# 4_-RF.net
KiCad netlist of a schematic drawn in Altium Designer
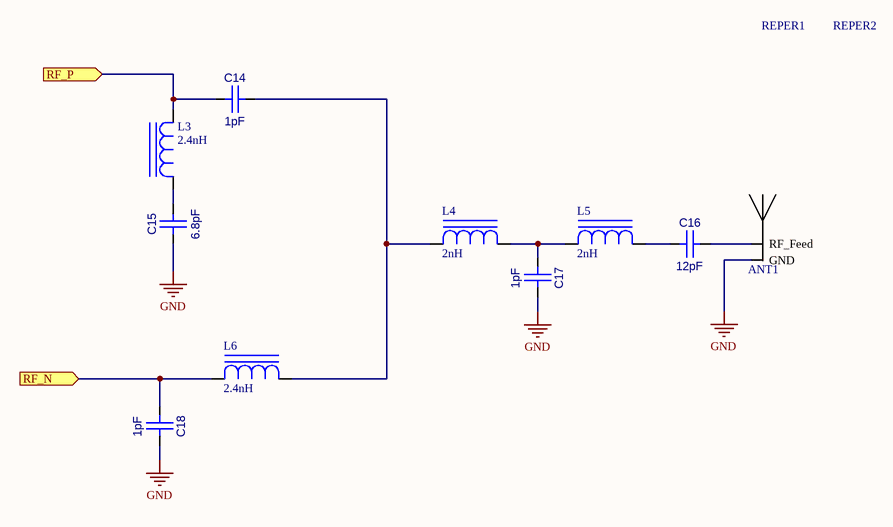
[diagram p0: [4]-RF.SchDoc]

(export (version "E")
  (design (tool "Eeschema 10.0.6"))
  (components
    (comp (ref "ANT1")
      (value "IFA_TI_2.4G_Reference")
      (footprint "ANT_IFA_2.4G_BEST")
      (libsource (lib "gprs_modem_2") (part "ANT_WiFi_IFA_BEST"))
    )
    (comp (ref "C14")
      (value "1pF")
      (footprint "CC0603")
      (description "CC0603")
      (libsource (lib "gprs_modem_2") (part "CC0603"))
    )
    (comp (ref "C15")
      (value "6.8pF")
      (footprint "CC0603")
      (description "CC0603")
      (libsource (lib "gprs_modem_2") (part "CC0603"))
    )
    (comp (ref "C16")
      (value "12pF")
      (footprint "CC0603")
      (description "CC0603")
      (libsource (lib "gprs_modem_2") (part "CC0603"))
    )
    (comp (ref "C17")
      (value "1pF")
      (footprint "CC0603")
      (description "CC0603")
      (libsource (lib "gprs_modem_2") (part "CC0603"))
    )
    (comp (ref "C18")
      (value "1pF")
      (footprint "CC0603")
      (description "CC0603")
      (libsource (lib "gprs_modem_2") (part "CC0603"))
    )
    (comp (ref "L3")
      (value "2.4nH")
      (footprint "L0402")
      (description "L0402")
      (libsource (lib "gprs_modem_2") (part "L0402"))
    )
    (comp (ref "L4")
      (value "2nH")
      (footprint "L0402")
      (description "L0402")
      (libsource (lib "gprs_modem_2") (part "L0402"))
    )
    (comp (ref "L5")
      (value "2nH")
      (footprint "L0402")
      (description "L0402")
      (libsource (lib "gprs_modem_2") (part "L0402"))
    )
    (comp (ref "L6")
      (value "2.4nH")
      (footprint "L0402")
      (description "L0402")
      (libsource (lib "gprs_modem_2") (part "L0402"))
    )
    (comp (ref "REPER1")
      (value "REPER1.2")
      (footprint "REPER1.2")
      (libsource (lib "gprs_modem_2") (part "REPER1.2"))
    )
    (comp (ref "REPER2")
      (value "REPER1.2")
      (footprint "REPER1.2")
      (libsource (lib "gprs_modem_2") (part "REPER1.2"))
    )
  )
  (nets
    (net (code "1") (name "/RF_N") (class "Default")
      (node (ref "C18") (pin "1") (pinfunction "A_1") (pintype "passive"))
      (node (ref "L6") (pin "1") (pinfunction "A_1") (pintype "passive"))
    )
    (net (code "2") (name "/RF_P") (class "Default")
      (node (ref "C14") (pin "1") (pinfunction "A_1") (pintype "passive"))
      (node (ref "L3") (pin "2") (pinfunction "C_2") (pintype "passive"))
    )
    (net (code "3") (name "GND") (class "Default")
      (node (ref "ANT1") (pin "2") (pinfunction "GND_2") (pintype "passive"))
      (node (ref "C15") (pin "1") (pinfunction "A_1") (pintype "passive"))
      (node (ref "C17") (pin "2") (pinfunction "B_2") (pintype "passive"))
      (node (ref "C18") (pin "2") (pinfunction "B_2") (pintype "passive"))
    )
    (net (code "4") (name "Net-(ANT1-RF_Feed)") (class "Default")
      (node (ref "ANT1") (pin "1") (pinfunction "RF_Feed_1") (pintype "passive"))
      (node (ref "C16") (pin "2") (pinfunction "B_2") (pintype "passive"))
    )
    (net (code "5") (name "Net-(C14-B)") (class "Default")
      (node (ref "C14") (pin "2") (pinfunction "B_2") (pintype "passive"))
      (node (ref "L4") (pin "1") (pinfunction "A_1") (pintype "passive"))
      (node (ref "L6") (pin "2") (pinfunction "C_2") (pintype "passive"))
    )
    (net (code "6") (name "Net-(C15-B)") (class "Default")
      (node (ref "C15") (pin "2") (pinfunction "B_2") (pintype "passive"))
      (node (ref "L3") (pin "1") (pinfunction "A_1") (pintype "passive"))
    )
    (net (code "7") (name "Net-(C16-A)") (class "Default")
      (node (ref "C16") (pin "1") (pinfunction "A_1") (pintype "passive"))
      (node (ref "L5") (pin "2") (pinfunction "C_2") (pintype "passive"))
    )
    (net (code "8") (name "Net-(C17-A)") (class "Default")
      (node (ref "C17") (pin "1") (pinfunction "A_1") (pintype "passive"))
      (node (ref "L4") (pin "2") (pinfunction "C_2") (pintype "passive"))
      (node (ref "L5") (pin "1") (pinfunction "A_1") (pintype "passive"))
    )
    (net (code "9") (name "unconnected-(REPER1-Pad1)") (class "Default")
      (node (ref "REPER1") (pin "1") (pintype "passive"))
    )
    (net (code "10") (name "unconnected-(REPER2-Pad1)") (class "Default")
      (node (ref "REPER2") (pin "1") (pintype "passive"))
    )
  )
)
